# linuxcard.net
KiCad netlist of a schematic drawn in Altium Designer
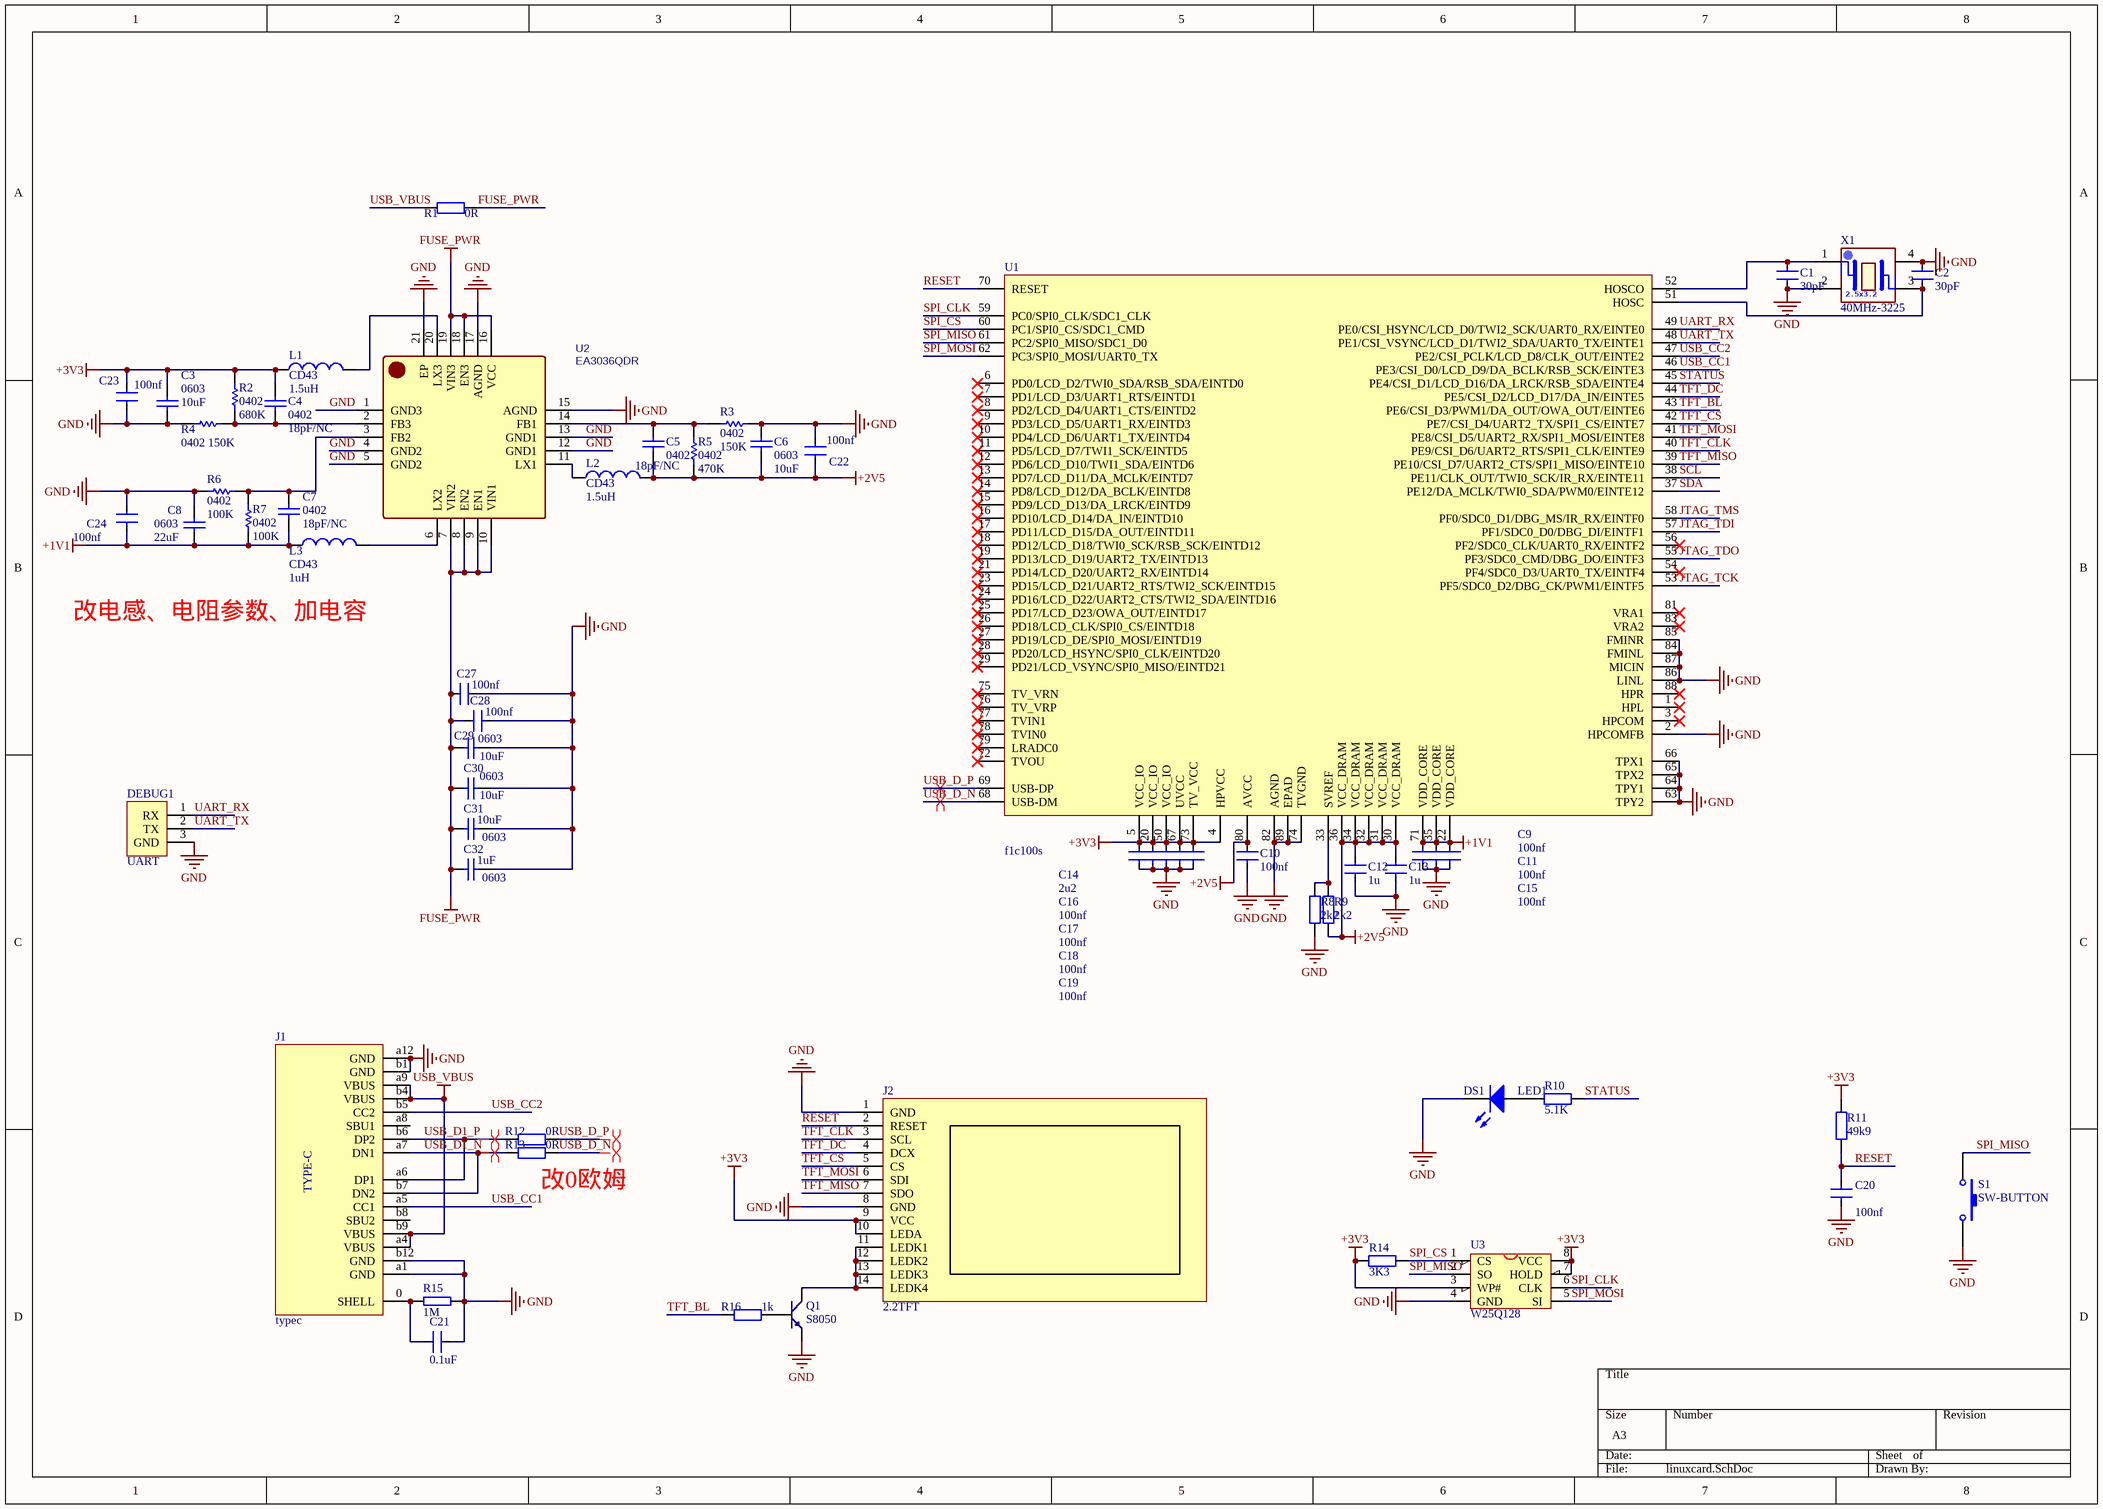
[diagram p0: linuxcard.SchDoc]

(export (version "E")
  (design (tool "Eeschema 10.0.6"))
  (components
    (comp (ref "C1")
      (value "30pF")
      (footprint "魔法王子:C0402")
      (description "普通小电容")
      (libsource (lib "LIB_MANGO") (part "CAP"))
    )
    (comp (ref "C2")
      (value "30pF")
      (footprint "魔法王子:C0402")
      (description "普通小电容")
      (libsource (lib "LIB_MANGO") (part "CAP"))
    )
    (comp (ref "C3")
      (value "0603")
      (footprint "pcb2D3D库1108:C0603")
      (description "Capacitor")
      (fields (field (name "ALTIUM_VALUE") "10uF") (field (name "PUBLISHER") "Altium Limited"))
      (libsource (lib "Miscellaneous Devices") (part "Cap"))
    )
    (comp (ref "C4")
      (value "0402")
      (footprint "pcb2D3D库1108:C0402")
      (description "Capacitor")
      (fields (field (name "ALTIUM_VALUE") "18pF/NC") (field (name "PUBLISHER") "Altium Limited"))
      (libsource (lib "Miscellaneous Devices") (part "Cap"))
    )
    (comp (ref "C5")
      (value "0402")
      (footprint "pcb2D3D库1108:C0402")
      (description "Capacitor")
      (fields (field (name "ALTIUM_VALUE") "18pF/NC") (field (name "PUBLISHER") "Altium Limited"))
      (libsource (lib "Miscellaneous Devices") (part "Cap"))
    )
    (comp (ref "C6")
      (value "0603")
      (footprint "pcb2D3D库1108:C0603")
      (description "Capacitor")
      (fields (field (name "ALTIUM_VALUE") "10uF") (field (name "PUBLISHER") "Altium Limited"))
      (libsource (lib "Miscellaneous Devices") (part "Cap"))
    )
    (comp (ref "C7")
      (value "0402")
      (footprint "pcb2D3D库1108:C0402")
      (description "Capacitor")
      (fields (field (name "ALTIUM_VALUE") "18pF/NC") (field (name "PUBLISHER") "Altium Limited"))
      (libsource (lib "Miscellaneous Devices") (part "Cap"))
    )
    (comp (ref "C8")
      (value "0603")
      (footprint "pcb2D3D库1108:C0603")
      (description "Capacitor")
      (fields (field (name "ALTIUM_VALUE") "22uF") (field (name "PUBLISHER") "Altium Limited"))
      (libsource (lib "Miscellaneous Devices") (part "Cap"))
    )
    (comp (ref "C9")
      (value "100nf")
      (footprint "魔法王子:C0402")
      (description "普通小电容")
      (libsource (lib "LIB_MANGO") (part "CAP"))
    )
    (comp (ref "C10")
      (value "100nf")
      (footprint "魔法王子:C0402")
      (description "普通小电容")
      (libsource (lib "LIB_MANGO") (part "CAP"))
    )
    (comp (ref "C11")
      (value "100nf")
      (footprint "魔法王子:C0402")
      (description "普通小电容")
      (libsource (lib "LIB_MANGO") (part "CAP"))
    )
    (comp (ref "C12")
      (value "1u")
      (footprint "魔法王子:C0402")
      (description "普通小电容")
      (libsource (lib "LIB_MANGO") (part "CAP"))
    )
    (comp (ref "C13")
      (value "1u")
      (footprint "魔法王子:C0402")
      (description "普通小电容")
      (libsource (lib "LIB_MANGO") (part "CAP"))
    )
    (comp (ref "C14")
      (value "2u2")
      (footprint "魔法王子:C0402")
      (description "普通小电容")
      (libsource (lib "LIB_MANGO") (part "CAP"))
    )
    (comp (ref "C15")
      (value "100nf")
      (footprint "魔法王子:C0402")
      (description "普通小电容")
      (libsource (lib "LIB_MANGO") (part "CAP"))
    )
    (comp (ref "C16")
      (value "100nf")
      (footprint "魔法王子:C0402")
      (description "普通小电容")
      (libsource (lib "LIB_MANGO") (part "CAP"))
    )
    (comp (ref "C17")
      (value "100nf")
      (footprint "魔法王子:C0402")
      (description "普通小电容")
      (libsource (lib "LIB_MANGO") (part "CAP"))
    )
    (comp (ref "C18")
      (value "100nf")
      (footprint "魔法王子:C0402")
      (description "普通小电容")
      (libsource (lib "LIB_MANGO") (part "CAP"))
    )
    (comp (ref "C19")
      (value "100nf")
      (footprint "魔法王子:C0402")
      (description "普通小电容")
      (libsource (lib "LIB_MANGO") (part "CAP"))
    )
    (comp (ref "C20")
      (value "100nf")
      (footprint "魔法王子:C0402")
      (description "普通小电容")
      (libsource (lib "LIB_MANGO") (part "CAP"))
    )
    (comp (ref "C21")
      (value "0.1uF")
      (footprint "魔法王子:C0402")
      (description "普通小电容")
      (libsource (lib "LIB_MANGO") (part "CAP"))
    )
    (comp (ref "C22")
      (value "100nf")
      (footprint "C0402")
      (description "普通小电容")
      (libsource (lib "LIB_MANGO") (part "CAP"))
    )
    (comp (ref "C23")
      (value "100nf")
      (footprint "C0402")
      (description "普通小电容")
      (libsource (lib "LIB_MANGO") (part "CAP"))
    )
    (comp (ref "C24")
      (value "100nf")
      (footprint "C0402")
      (description "普通小电容")
      (libsource (lib "LIB_MANGO") (part "CAP"))
    )
    (comp (ref "C27")
      (value "100nf")
      (footprint "C0402")
      (description "普通小电容")
      (libsource (lib "LIB_MANGO") (part "CAP"))
    )
    (comp (ref "C28")
      (value "100nf")
      (footprint "魔法王子:C0402")
      (description "普通小电容")
      (libsource (lib "LIB_MANGO") (part "CAP"))
    )
    (comp (ref "C29")
      (value "0603")
      (footprint "C0603")
      (description "Capacitor")
      (fields (field (name "ALTIUM_VALUE") "10uF") (field (name "PUBLISHER") "Altium Limited"))
      (libsource (lib "Miscellaneous Devices") (part "Cap"))
    )
    (comp (ref "C30")
      (value "0603")
      (footprint "C0603")
      (description "Capacitor")
      (fields (field (name "ALTIUM_VALUE") "10uF") (field (name "PUBLISHER") "Altium Limited"))
      (libsource (lib "Miscellaneous Devices") (part "Cap"))
    )
    (comp (ref "C31")
      (value "0603")
      (footprint "C0603")
      (description "Capacitor")
      (fields (field (name "ALTIUM_VALUE") "10uF") (field (name "PUBLISHER") "Altium Limited"))
      (libsource (lib "Miscellaneous Devices") (part "Cap"))
    )
    (comp (ref "C32")
      (value "0603")
      (footprint "C0603")
      (description "Capacitor")
      (fields (field (name "ALTIUM_VALUE") "1uF") (field (name "PUBLISHER") "Altium Limited"))
      (libsource (lib "Miscellaneous Devices") (part "Cap"))
    )
    (comp (ref "DEBUG1") (value "UART") (footprint "魔法王子:UART") (libsource (lib "魔法王子") (part "UART_OUT")))
    (comp (ref "DS1")
      (value "LED1")
      (footprint "pcb2D3D库1108:LED0805")
      (description "Typical RED, GREEN, YELLOW, AMBER GaAs LED")
      (fields (field (name "PUBLISHER") "Altium Limited"))
      (libsource (lib "Explorer STM32F407封装库") (part "LED2"))
    )
    (comp (ref "J1") (value "typec") (footprint "魔法王子:USBC") (libsource (lib "魔法王子") (part "USBC")))
    (comp (ref "J2") (value "2.2TFT") (footprint "魔法王子:2.2TFT") (libsource (lib "魔法王子") (part "TFT2.2")))
    (comp (ref "L1")
      (value "CD43")
      (footprint "pcb2D3D库1108:L1210")
      (fields (field (name "ALTIUM_VALUE") "1.5uH") (field (name "PUBLISHER") "Altium Limited"))
      (libsource (lib "Miscellaneous Devices") (part "Inductor"))
    )
    (comp (ref "L2")
      (value "CD43")
      (footprint "pcb2D3D库1108:L1210")
      (fields (field (name "ALTIUM_VALUE") "1.5uH") (field (name "PUBLISHER") "Altium Limited"))
      (libsource (lib "Miscellaneous Devices") (part "Inductor"))
    )
    (comp (ref "L3")
      (value "CD43")
      (footprint "pcb2D3D库1108:L1210")
      (fields (field (name "ALTIUM_VALUE") "1uH") (field (name "PUBLISHER") "Altium Limited"))
      (libsource (lib "Miscellaneous Devices") (part "Inductor"))
    )
    (comp (ref "Q1")
      (value "S8050")
      (footprint "魔法王子:sot-23")
      (description "8050/BCW846/BCW847")
      (libsource (lib "Explorer STM32F407封装库") (part "NPN"))
    )
    (comp (ref "R1")
      (value "0R")
      (footprint "pcb2D3D库1108:R0805")
      (description "普通电阻")
      (libsource (lib "") (part "RES_1"))
    )
    (comp (ref "R2")
      (value "0402")
      (footprint "pcb2D3D库1108:R0402")
      (fields (field (name "ALTIUM_VALUE") "680K") (field (name "PUBLISHER") "Altium Limited"))
      (libsource (lib "Miscellaneous Devices") (part "Res1"))
    )
    (comp (ref "R3")
      (value "0402")
      (footprint "pcb2D3D库1108:R0402")
      (description "Resistor")
      (fields (field (name "ALTIUM_VALUE") "150K") (field (name "PUBLISHER") "Altium Limited"))
      (libsource (lib "Miscellaneous Devices") (part "Res1"))
    )
    (comp (ref "R4")
      (value "0402")
      (footprint "pcb2D3D库1108:R0402")
      (description "Resistor")
      (fields (field (name "ALTIUM_VALUE") "150K") (field (name "PUBLISHER") "Altium Limited"))
      (libsource (lib "Miscellaneous Devices") (part "Res1"))
    )
    (comp (ref "R5")
      (value "0402")
      (footprint "pcb2D3D库1108:R0402")
      (fields (field (name "ALTIUM_VALUE") "470K") (field (name "PUBLISHER") "Altium Limited"))
      (libsource (lib "Miscellaneous Devices") (part "Res1"))
    )
    (comp (ref "R6")
      (value "0402")
      (footprint "pcb2D3D库1108:R0402")
      (fields (field (name "ALTIUM_VALUE") "100K") (field (name "PUBLISHER") "Altium Limited"))
      (libsource (lib "Miscellaneous Devices") (part "Res1"))
    )
    (comp (ref "R7")
      (value "0402")
      (footprint "pcb2D3D库1108:R0402")
      (fields (field (name "ALTIUM_VALUE") "100K") (field (name "PUBLISHER") "Altium Limited"))
      (libsource (lib "Miscellaneous Devices") (part "Res1"))
    )
    (comp (ref "R8")
      (value "2k2")
      (footprint "魔法王子:R0402")
      (description "普通电阻")
      (libsource (lib "LIB_MANGO") (part "RES"))
    )
    (comp (ref "R9")
      (value "2k2")
      (footprint "魔法王子:R0402")
      (description "普通电阻")
      (libsource (lib "LIB_MANGO") (part "RES"))
    )
    (comp (ref "R10")
      (value "5.1K")
      (footprint "魔法王子:R0402")
      (description "普通电阻")
      (libsource (lib "") (part "RES_1"))
    )
    (comp (ref "R11")
      (value "49k9")
      (footprint "魔法王子:R0402")
      (description "普通电阻")
      (libsource (lib "LIB_MANGO") (part "RES"))
    )
    (comp (ref "R12")
      (value "0R")
      (footprint "魔法王子:R0402")
      (description "普通电阻")
      (libsource (lib "") (part "RES_1"))
    )
    (comp (ref "R13")
      (value "0R")
      (footprint "魔法王子:R0402")
      (description "普通电阻")
      (libsource (lib "") (part "RES_1"))
    )
    (comp (ref "R14")
      (value "3K3")
      (footprint "魔法王子:R0402")
      (description "普通电阻")
      (libsource (lib "") (part "RES_2"))
    )
    (comp (ref "R15") (value "1M") (footprint "魔法王子:R0402") (libsource (lib "电阻") (part "0805正")))
    (comp (ref "R16")
      (value "1k")
      (footprint "魔法王子:R0402")
      (description "普通电阻")
      (libsource (lib "") (part "RES_1"))
    )
    (comp (ref "S1")
      (value "SW-BUTTON")
      (footprint "pcb2D3D库1108:KEY-SMD1")
      (libsource (lib "LIB_MANGO") (part "SW-BUTTON"))
    )
    (comp (ref "U1") (value "f1c100s") (footprint "魔法王子:F1C100S") (libsource (lib "魔法王子") (part "f1c100s")))
    (comp (ref "U2")
      (value "EA3036QDR")
      (footprint "魔法王子:ea3036")
      (fields (field (name "BOM_SUPPLIER PART") "C111587"))
      (libsource (lib "IC") (part "EA3036QDR"))
    )
    (comp (ref "U3")
      (value "W25Q128")
      (footprint "pcb2D3D库1108:SOIC8")
      (description "W25X16;SST25VF016;MX25L1605")
      (libsource (lib "Explorer STM32F407封装库") (part "W25X16"))
    )
    (comp (ref "X1")
      (value "40MHz-3225")
      (footprint "pcb2D3D库1108:XTAL-3225")
      (libsource (lib "LIB_MANGO") (part "XTAL3225"))
    )
  )
  (nets
    (net (code "1") (name "+1V1") (class "Default")
      (node (ref "C11") (pin "2") (pinfunction "2_2") (pintype "passive"))
      (node (ref "C15") (pin "2") (pinfunction "2_2") (pintype "passive"))
      (node (ref "C24") (pin "1") (pinfunction "1_1") (pintype "passive"))
      (node (ref "C7") (pin "1") (pinfunction "1_1") (pintype "passive"))
      (node (ref "C8") (pin "2") (pinfunction "2_2") (pintype "passive"))
      (node (ref "C9") (pin "2") (pinfunction "2_2") (pintype "passive"))
      (node (ref "L3") (pin "1") (pinfunction "1_1") (pintype "passive"))
      (node (ref "R7") (pin "1") (pinfunction "1_1") (pintype "passive"))
      (node (ref "U1") (pin "22") (pinfunction "VDD_CORE_22") (pintype "passive"))
      (node (ref "U1") (pin "35") (pinfunction "VDD_CORE_35") (pintype "passive"))
      (node (ref "U1") (pin "71") (pinfunction "VDD_CORE_71") (pintype "passive"))
    )
    (net (code "2") (name "+2V5") (class "Default")
      (node (ref "C10") (pin "2") (pinfunction "2_2") (pintype "passive"))
      (node (ref "C12") (pin "2") (pinfunction "2_2") (pintype "passive"))
      (node (ref "C13") (pin "2") (pinfunction "2_2") (pintype "passive"))
      (node (ref "C22") (pin "1") (pinfunction "1_1") (pintype "passive"))
      (node (ref "C5") (pin "1") (pinfunction "1_1") (pintype "passive"))
      (node (ref "C6") (pin "1") (pinfunction "1_1") (pintype "passive"))
      (node (ref "L2") (pin "2") (pinfunction "2_2") (pintype "passive"))
      (node (ref "R5") (pin "2") (pinfunction "2_2") (pintype "passive"))
      (node (ref "R9") (pin "2") (pinfunction "2_2") (pintype "passive"))
      (node (ref "U1") (pin "30") (pinfunction "VCC_DRAM_30") (pintype "passive"))
      (node (ref "U1") (pin "31") (pinfunction "VCC_DRAM_31") (pintype "passive"))
      (node (ref "U1") (pin "32") (pinfunction "VCC_DRAM_32") (pintype "passive"))
      (node (ref "U1") (pin "34") (pinfunction "VCC_DRAM_34") (pintype "passive"))
      (node (ref "U1") (pin "36") (pinfunction "VCC_DRAM_36") (pintype "passive"))
      (node (ref "U1") (pin "80") (pinfunction "AVCC_80") (pintype "passive"))
    )
    (net (code "3") (name "+3V3") (class "Default")
      (node (ref "C14") (pin "2") (pinfunction "2_2") (pintype "passive"))
      (node (ref "C16") (pin "2") (pinfunction "2_2") (pintype "passive"))
      (node (ref "C17") (pin "2") (pinfunction "2_2") (pintype "passive"))
      (node (ref "C18") (pin "2") (pinfunction "2_2") (pintype "passive"))
      (node (ref "C19") (pin "2") (pinfunction "2_2") (pintype "passive"))
      (node (ref "C23") (pin "2") (pinfunction "2_2") (pintype "passive"))
      (node (ref "C3") (pin "1") (pinfunction "1_1") (pintype "passive"))
      (node (ref "C4") (pin "1") (pinfunction "1_1") (pintype "passive"))
      (node (ref "J2") (pin "10") (pinfunction "LEDA_10") (pintype "passive"))
      (node (ref "J2") (pin "9") (pinfunction "VCC_9") (pintype "passive"))
      (node (ref "L1") (pin "1") (pinfunction "1_1") (pintype "passive"))
      (node (ref "R11") (pin "1") (pinfunction "1_1") (pintype "passive"))
      (node (ref "R14") (pin "2") (pinfunction "2_2") (pintype "passive"))
      (node (ref "R2") (pin "2") (pinfunction "2_2") (pintype "passive"))
      (node (ref "U1") (pin "20") (pinfunction "VCC_IO_20") (pintype "passive"))
      (node (ref "U1") (pin "4") (pinfunction "HPVCC_4") (pintype "passive"))
      (node (ref "U1") (pin "5") (pinfunction "VCC_IO_5") (pintype "passive"))
      (node (ref "U1") (pin "50") (pinfunction "VCC_IO_50") (pintype "passive"))
      (node (ref "U1") (pin "67") (pinfunction "UVCC_67") (pintype "passive"))
      (node (ref "U1") (pin "73") (pinfunction "TV_VCC_73") (pintype "passive"))
      (node (ref "U3") (pin "3") (pinfunction "WP#_3") (pintype "passive"))
      (node (ref "U3") (pin "7") (pinfunction "HOLD_7") (pintype "passive"))
      (node (ref "U3") (pin "8") (pinfunction "VCC_8") (pintype "passive"))
    )
    (net (code "4") (name "/JTAG_TCK") (class "Default")
      (node (ref "U1") (pin "53") (pinfunction "PF5/SDC0_D2/DBG_CK/PWM1/EINTF5_53") (pintype "passive"))
    )
    (net (code "5") (name "/JTAG_TDI") (class "Default")
      (node (ref "U1") (pin "57") (pinfunction "PF1/SDC0_D0/DBG_DI/EINTF1_57") (pintype "passive"))
    )
    (net (code "6") (name "/JTAG_TDO") (class "Default")
      (node (ref "U1") (pin "55") (pinfunction "PF3/SDC0_CMD/DBG_DO/EINTF3_55") (pintype "passive"))
    )
    (net (code "7") (name "/JTAG_TMS") (class "Default")
      (node (ref "U1") (pin "58") (pinfunction "PF0/SDC0_D1/DBG_MS/IR_RX/EINTF0_58") (pintype "passive"))
    )
    (net (code "8") (name "/RESET") (class "Default")
      (node (ref "C20") (pin "2") (pinfunction "2_2") (pintype "passive"))
      (node (ref "J2") (pin "2") (pinfunction "RESET_2") (pintype "passive"))
      (node (ref "R11") (pin "2") (pinfunction "2_2") (pintype "passive"))
      (node (ref "U1") (pin "70") (pinfunction "RESET_70") (pintype "passive"))
    )
    (net (code "9") (name "/SCL") (class "Default")
      (node (ref "U1") (pin "38") (pinfunction "PE11/CLK_OUT/TWI0_SCK/IR_RX/EINTE11_38") (pintype "passive"))
    )
    (net (code "10") (name "/SDA") (class "Default")
      (node (ref "U1") (pin "37") (pinfunction "PE12/DA_MCLK/TWI0_SDA/PWM0/EINTE12_37") (pintype "passive"))
    )
    (net (code "11") (name "/SPI_CLK") (class "Default")
      (node (ref "U1") (pin "59") (pinfunction "PC0/SPI0_CLK/SDC1_CLK_59") (pintype "passive"))
      (node (ref "U3") (pin "6") (pinfunction "CLK_6") (pintype "passive"))
    )
    (net (code "12") (name "/SPI_CS") (class "Default")
      (node (ref "R14") (pin "1") (pinfunction "1_1") (pintype "passive"))
      (node (ref "U1") (pin "60") (pinfunction "PC1/SPI0_CS/SDC1_CMD_60") (pintype "passive"))
      (node (ref "U3") (pin "1") (pinfunction "CS_1") (pintype "passive"))
    )
    (net (code "13") (name "/SPI_MISO") (class "Default")
      (node (ref "S1") (pin "1") (pinfunction "1_1") (pintype "passive"))
      (node (ref "U1") (pin "61") (pinfunction "PC2/SPI0_MISO/SDC1_D0_61") (pintype "passive"))
      (node (ref "U3") (pin "2") (pinfunction "SO_2") (pintype "passive"))
    )
    (net (code "14") (name "/SPI_MOSI") (class "Default")
      (node (ref "U1") (pin "62") (pinfunction "PC3/SPI0_MOSI/UART0_TX_62") (pintype "passive"))
      (node (ref "U3") (pin "5") (pinfunction "SI_5") (pintype "passive"))
    )
    (net (code "15") (name "/STATUS") (class "Default")
      (node (ref "R10") (pin "2") (pinfunction "2_2") (pintype "passive"))
      (node (ref "U1") (pin "45") (pinfunction "PE4/CSI_D1/LCD_D16/DA_LRCK/RSB_SDA/EINTE4_45") (pintype "passive"))
    )
    (net (code "16") (name "/TFT_BL") (class "Default")
      (node (ref "R16") (pin "1") (pinfunction "1_1") (pintype "passive"))
      (node (ref "U1") (pin "43") (pinfunction "PE6/CSI_D3/PWM1/DA_OUT/OWA_OUT/EINTE6_43") (pintype "passive"))
    )
    (net (code "17") (name "/TFT_CLK") (class "Default")
      (node (ref "J2") (pin "3") (pinfunction "SCL_3") (pintype "passive"))
      (node (ref "U1") (pin "40") (pinfunction "PE9/CSI_D6/UART2_RTS/SPI1_CLK/EINTE9_40") (pintype "passive"))
    )
    (net (code "18") (name "/TFT_CS") (class "Default")
      (node (ref "J2") (pin "5") (pinfunction "CS_5") (pintype "passive"))
      (node (ref "U1") (pin "42") (pinfunction "PE7/CSI_D4/UART2_TX/SPI1_CS/EINTE7_42") (pintype "passive"))
    )
    (net (code "19") (name "/TFT_DC") (class "Default")
      (node (ref "J2") (pin "4") (pinfunction "DCX_4") (pintype "passive"))
      (node (ref "U1") (pin "44") (pinfunction "PE5/CSI_D2/LCD_D17/DA_IN/EINTE5_44") (pintype "passive"))
    )
    (net (code "20") (name "/TFT_MISO") (class "Default")
      (node (ref "J2") (pin "7") (pinfunction "SDO_7") (pintype "passive"))
      (node (ref "U1") (pin "39") (pinfunction "PE10/CSI_D7/UART2_CTS/SPI1_MISO/EINTE10_39") (pintype "passive"))
    )
    (net (code "21") (name "/TFT_MOSI") (class "Default")
      (node (ref "J2") (pin "6") (pinfunction "SDI_6") (pintype "passive"))
      (node (ref "U1") (pin "41") (pinfunction "PE8/CSI_D5/UART2_RX/SPI1_MOSI/EINTE8_41") (pintype "passive"))
    )
    (net (code "22") (name "/UART_RX") (class "Default")
      (node (ref "DEBUG1") (pin "1") (pinfunction "RX_1") (pintype "passive"))
      (node (ref "U1") (pin "49") (pinfunction "PE0/CSI_HSYNC/LCD_D0/TWI2_SCK/UART0_RX/EINTE0_49") (pintype "passive"))
    )
    (net (code "23") (name "/UART_TX") (class "Default")
      (node (ref "DEBUG1") (pin "2") (pinfunction "TX_2") (pintype "passive"))
      (node (ref "U1") (pin "48") (pinfunction "PE1/CSI_VSYNC/LCD_D1/TWI2_SDA/UART0_TX/EINTE1_48") (pintype "passive"))
    )
    (net (code "24") (name "/USB_CC1") (class "Default")
      (node (ref "J1") (pin "a5") (pinfunction "CC1_a5") (pintype "passive"))
      (node (ref "U1") (pin "46") (pinfunction "PE3/CSI_D0/LCD_D9/DA_BCLK/RSB_SCK/EINTE3_46") (pintype "passive"))
    )
    (net (code "25") (name "/USB_CC2") (class "Default")
      (node (ref "J1") (pin "b5") (pinfunction "CC2_b5") (pintype "passive"))
      (node (ref "U1") (pin "47") (pinfunction "PE2/CSI_PCLK/LCD_D8/CLK_OUT/EINTE2_47") (pintype "passive"))
    )
    (net (code "26") (name "/USB_D1_N") (class "Default")
      (node (ref "J1") (pin "a7") (pinfunction "DN1_a7") (pintype "passive"))
      (node (ref "J1") (pin "b7") (pinfunction "DN2_b7") (pintype "passive"))
      (node (ref "R13") (pin "1") (pinfunction "1_1") (pintype "passive"))
    )
    (net (code "27") (name "/USB_D1_P") (class "Default")
      (node (ref "J1") (pin "a6") (pinfunction "DP1_a6") (pintype "passive"))
      (node (ref "J1") (pin "b6") (pinfunction "DP2_b6") (pintype "passive"))
      (node (ref "R12") (pin "1") (pinfunction "1_1") (pintype "passive"))
    )
    (net (code "28") (name "/USB_D_N") (class "Default")
      (node (ref "R13") (pin "2") (pinfunction "2_2") (pintype "passive"))
      (node (ref "U1") (pin "68") (pinfunction "USB-DM_68") (pintype "passive"))
    )
    (net (code "29") (name "/USB_D_P") (class "Default")
      (node (ref "R12") (pin "2") (pinfunction "2_2") (pintype "passive"))
      (node (ref "U1") (pin "69") (pinfunction "USB-DP_69") (pintype "passive"))
    )
    (net (code "30") (name "FUSE_PWR") (class "Default")
      (node (ref "C27") (pin "2") (pinfunction "2_2") (pintype "passive"))
      (node (ref "C28") (pin "2") (pinfunction "2_2") (pintype "passive"))
      (node (ref "C29") (pin "1") (pinfunction "1_1") (pintype "passive"))
      (node (ref "C30") (pin "1") (pinfunction "1_1") (pintype "passive"))
      (node (ref "C31") (pin "1") (pinfunction "1_1") (pintype "passive"))
      (node (ref "C32") (pin "1") (pinfunction "1_1") (pintype "passive"))
      (node (ref "R1") (pin "2") (pinfunction "2_2") (pintype "passive"))
      (node (ref "U2") (pin "10") (pinfunction "VIN1_10") (pintype "passive"))
      (node (ref "U2") (pin "16") (pinfunction "VCC_16") (pintype "passive"))
      (node (ref "U2") (pin "18") (pinfunction "EN3_18") (pintype "passive"))
      (node (ref "U2") (pin "19") (pinfunction "VIN3_19") (pintype "passive"))
      (node (ref "U2") (pin "7") (pinfunction "VIN2_7") (pintype "passive"))
      (node (ref "U2") (pin "8") (pinfunction "EN2_8") (pintype "passive"))
      (node (ref "U2") (pin "9") (pinfunction "EN1_9") (pintype "passive"))
    )
    (net (code "31") (name "GND") (class "Default")
      (node (ref "C1") (pin "1") (pinfunction "1_1") (pintype "passive"))
      (node (ref "C10") (pin "1") (pinfunction "1_1") (pintype "passive"))
      (node (ref "C11") (pin "1") (pinfunction "1_1") (pintype "passive"))
      (node (ref "C12") (pin "1") (pinfunction "1_1") (pintype "passive"))
      (node (ref "C13") (pin "1") (pinfunction "1_1") (pintype "passive"))
      (node (ref "C14") (pin "1") (pinfunction "1_1") (pintype "passive"))
      (node (ref "C15") (pin "1") (pinfunction "1_1") (pintype "passive"))
      (node (ref "C16") (pin "1") (pinfunction "1_1") (pintype "passive"))
      (node (ref "C17") (pin "1") (pinfunction "1_1") (pintype "passive"))
      (node (ref "C18") (pin "1") (pinfunction "1_1") (pintype "passive"))
      (node (ref "C19") (pin "1") (pinfunction "1_1") (pintype "passive"))
      (node (ref "C2") (pin "2") (pinfunction "2_2") (pintype "passive"))
      (node (ref "C20") (pin "1") (pinfunction "1_1") (pintype "passive"))
      (node (ref "C21") (pin "1") (pinfunction "1_1") (pintype "passive"))
      (node (ref "C22") (pin "2") (pinfunction "2_2") (pintype "passive"))
      (node (ref "C23") (pin "1") (pinfunction "1_1") (pintype "passive"))
      (node (ref "C24") (pin "2") (pinfunction "2_2") (pintype "passive"))
      (node (ref "C27") (pin "1") (pinfunction "1_1") (pintype "passive"))
      (node (ref "C28") (pin "1") (pinfunction "1_1") (pintype "passive"))
      (node (ref "C29") (pin "2") (pinfunction "2_2") (pintype "passive"))
      (node (ref "C3") (pin "2") (pinfunction "2_2") (pintype "passive"))
      (node (ref "C30") (pin "2") (pinfunction "2_2") (pintype "passive"))
      (node (ref "C31") (pin "2") (pinfunction "2_2") (pintype "passive"))
      (node (ref "C32") (pin "2") (pinfunction "2_2") (pintype "passive"))
      (node (ref "C6") (pin "2") (pinfunction "2_2") (pintype "passive"))
      (node (ref "C8") (pin "1") (pinfunction "1_1") (pintype "passive"))
      (node (ref "C9") (pin "1") (pinfunction "1_1") (pintype "passive"))
      (node (ref "DEBUG1") (pin "3") (pinfunction "GND_3") (pintype "passive"))
      (node (ref "DS1") (pin "2") (pinfunction "K_2") (pintype "passive"))
      (node (ref "J1") (pin "a1") (pinfunction "GND_a1") (pintype "passive"))
      (node (ref "J1") (pin "a12") (pinfunction "GND_a12") (pintype "passive"))
      (node (ref "J1") (pin "b1") (pinfunction "GND_b1") (pintype "passive"))
      (node (ref "J1") (pin "b12") (pinfunction "GND_b12") (pintype "passive"))
      (node (ref "J2") (pin "1") (pinfunction "GND_1") (pintype "passive"))
      (node (ref "J2") (pin "8") (pinfunction "GND_8") (pintype "passive"))
      (node (ref "Q1") (pin "1") (pinfunction "E_1") (pintype "passive"))
      (node (ref "R15") (pin "1") (pinfunction "1_1") (pintype "passive"))
      (node (ref "R3") (pin "2") (pinfunction "2_2") (pintype "passive"))
      (node (ref "R4") (pin "2") (pinfunction "2_2") (pintype "passive"))
      (node (ref "R6") (pin "2") (pinfunction "2_2") (pintype "passive"))
      (node (ref "R8") (pin "2") (pinfunction "2_2") (pintype "passive"))
      (node (ref "S1") (pin "2") (pinfunction "2_2") (pintype "passive"))
      (node (ref "U1") (pin "2") (pinfunction "HPCOMFB_2") (pintype "passive"))
      (node (ref "U1") (pin "63") (pinfunction "TPY2_63") (pintype "passive"))
      (node (ref "U1") (pin "64") (pinfunction "TPY1_64") (pintype "passive"))
      (node (ref "U1") (pin "65") (pinfunction "TPX2_65") (pintype "passive"))
      (node (ref "U1") (pin "66") (pinfunction "TPX1_66") (pintype "passive"))
      (node (ref "U1") (pin "74") (pinfunction "TVGND_74") (pintype "passive"))
      (node (ref "U1") (pin "82") (pinfunction "AGND_82") (pintype "passive"))
      (node (ref "U1") (pin "84") (pinfunction "FMINL_84") (pintype "passive"))
      (node (ref "U1") (pin "85") (pinfunction "FMINR_85") (pintype "passive"))
      (node (ref "U1") (pin "86") (pinfunction "LINL_86") (pintype "passive"))
      (node (ref "U1") (pin "87") (pinfunction "MICIN_87") (pintype "passive"))
      (node (ref "U1") (pin "89") (pinfunction "EPAD_89") (pintype "passive"))
      (node (ref "U2") (pin "1") (pinfunction "GND3_1") (pintype "passive"))
      (node (ref "U2") (pin "12") (pinfunction "GND1_12") (pintype "passive"))
      (node (ref "U2") (pin "13") (pinfunction "GND1_13") (pintype "passive"))
      (node (ref "U2") (pin "15") (pinfunction "AGND_15") (pintype "passive"))
      (node (ref "U2") (pin "17") (pinfunction "AGND_17") (pintype "passive"))
      (node (ref "U2") (pin "21") (pinfunction "EP_21") (pintype "passive"))
      (node (ref "U2") (pin "4") (pinfunction "GND2_4") (pintype "passive"))
      (node (ref "U2") (pin "5") (pinfunction "GND2_5") (pintype "passive"))
      (node (ref "U3") (pin "4") (pinfunction "GND_4") (pintype "passive"))
      (node (ref "X1") (pin "2") (pinfunction "NC1_2") (pintype "passive"))
      (node (ref "X1") (pin "4") (pinfunction "NC2_4") (pintype "passive"))
    )
    (net (code "32") (name "Net-(DS1-A)") (class "Default")
      (node (ref "DS1") (pin "1") (pinfunction "A_1") (pintype "passive"))
      (node (ref "R10") (pin "1") (pinfunction "1_1") (pintype "passive"))
    )
    (net (code "33") (name "Net-(J1-SHELL)") (class "Default")
      (node (ref "C21") (pin "2") (pinfunction "2_2") (pintype "passive"))
      (node (ref "J1") (pin "0") (pinfunction "SHELL_0") (pintype "passive"))
      (node (ref "R15") (pin "2") (pinfunction "2_2") (pintype "passive"))
    )
    (net (code "34") (name "Net-(J2-LEDK1)") (class "Default")
      (node (ref "J2") (pin "11") (pinfunction "LEDK1_11") (pintype "passive"))
      (node (ref "J2") (pin "12") (pinfunction "LEDK2_12") (pintype "passive"))
      (node (ref "J2") (pin "13") (pinfunction "LEDK3_13") (pintype "passive"))
      (node (ref "J2") (pin "14") (pinfunction "LEDK4_14") (pintype "passive"))
      (node (ref "Q1") (pin "3") (pinfunction "C_3") (pintype "passive"))
    )
    (net (code "35") (name "Net-(Q1-B)") (class "Default")
      (node (ref "Q1") (pin "2") (pinfunction "B_2") (pintype "passive"))
      (node (ref "R16") (pin "2") (pinfunction "2_2") (pintype "passive"))
    )
    (net (code "36") (name "Net-(U1-HOSC)") (class "Default")
      (node (ref "C2") (pin "1") (pinfunction "1_1") (pintype "passive"))
      (node (ref "U1") (pin "51") (pinfunction "HOSC_51") (pintype "passive"))
      (node (ref "X1") (pin "3") (pinfunction "X2_3") (pintype "passive"))
    )
    (net (code "37") (name "Net-(U1-HOSCO)") (class "Default")
      (node (ref "C1") (pin "2") (pinfunction "2_2") (pintype "passive"))
      (node (ref "U1") (pin "52") (pinfunction "HOSCO_52") (pintype "passive"))
      (node (ref "X1") (pin "1") (pinfunction "X1_1") (pintype "passive"))
    )
    (net (code "38") (name "Net-(U1-SVREF)") (class "Default")
      (node (ref "R8") (pin "1") (pinfunction "1_1") (pintype "passive"))
      (node (ref "R9") (pin "1") (pinfunction "1_1") (pintype "passive"))
      (node (ref "U1") (pin "33") (pinfunction "SVREF_33") (pintype "passive"))
    )
    (net (code "39") (name "Net-(U2-FB1)") (class "Default")
      (node (ref "C5") (pin "2") (pinfunction "2_2") (pintype "passive"))
      (node (ref "R3") (pin "1") (pinfunction "1_1") (pintype "passive"))
      (node (ref "R5") (pin "1") (pinfunction "1_1") (pintype "passive"))
      (node (ref "U2") (pin "14") (pinfunction "FB1_14") (pintype "passive"))
    )
    (net (code "40") (name "Net-(U2-FB2)") (class "Default")
      (node (ref "C7") (pin "2") (pinfunction "2_2") (pintype "passive"))
      (node (ref "R6") (pin "1") (pinfunction "1_1") (pintype "passive"))
      (node (ref "R7") (pin "2") (pinfunction "2_2") (pintype "passive"))
      (node (ref "U2") (pin "3") (pinfunction "FB2_3") (pintype "passive"))
    )
    (net (code "41") (name "Net-(U2-FB3)") (class "Default")
      (node (ref "C4") (pin "2") (pinfunction "2_2") (pintype "passive"))
      (node (ref "R2") (pin "1") (pinfunction "1_1") (pintype "passive"))
      (node (ref "R4") (pin "1") (pinfunction "1_1") (pintype "passive"))
      (node (ref "U2") (pin "2") (pinfunction "FB3_2") (pintype "passive"))
    )
    (net (code "42") (name "Net-(U2-LX1)") (class "Default")
      (node (ref "L2") (pin "1") (pinfunction "1_1") (pintype "passive"))
      (node (ref "U2") (pin "11") (pinfunction "LX1_11") (pintype "passive"))
    )
    (net (code "43") (name "Net-(U2-LX2)") (class "Default")
      (node (ref "L3") (pin "2") (pinfunction "2_2") (pintype "passive"))
      (node (ref "U2") (pin "6") (pinfunction "LX2_6") (pintype "passive"))
    )
    (net (code "44") (name "Net-(U2-LX3)") (class "Default")
      (node (ref "L1") (pin "2") (pinfunction "2_2") (pintype "passive"))
      (node (ref "U2") (pin "20") (pinfunction "LX3_20") (pintype "passive"))
    )
    (net (code "45") (name "USB_VBUS") (class "Default")
      (node (ref "J1") (pin "a4") (pinfunction "VBUS_a4") (pintype "passive"))
      (node (ref "J1") (pin "a9") (pinfunction "VBUS_a9") (pintype "passive"))
      (node (ref "J1") (pin "b4") (pinfunction "VBUS_b4") (pintype "passive"))
      (node (ref "J1") (pin "b9") (pinfunction "VBUS_b9") (pintype "passive"))
      (node (ref "R1") (pin "1") (pinfunction "1_1") (pintype "passive"))
    )
    (net (code "46") (name "unconnected-(J1-SBU1-Pada8)") (class "Default")
      (node (ref "J1") (pin "a8") (pinfunction "SBU1_a8") (pintype "passive"))
    )
    (net (code "47") (name "unconnected-(J1-SBU2-Padb8)") (class "Default")
      (node (ref "J1") (pin "b8") (pinfunction "SBU2_b8") (pintype "passive"))
    )
    (net (code "48") (name "unconnected-(U1-HPCOM-Pad3)") (class "Default")
      (node (ref "U1") (pin "3") (pinfunction "HPCOM_3") (pintype "passive+no_connect"))
    )
    (net (code "49") (name "unconnected-(U1-HPL-Pad1)") (class "Default")
      (node (ref "U1") (pin "1") (pinfunction "HPL_1") (pintype "passive+no_connect"))
    )
    (net (code "50") (name "unconnected-(U1-HPR-Pad88)") (class "Default")
      (node (ref "U1") (pin "88") (pinfunction "HPR_88") (pintype "passive+no_connect"))
    )
    (net (code "51") (name "unconnected-(U1-LRADC0-Pad79)") (class "Default")
      (node (ref "U1") (pin "79") (pinfunction "LRADC0_79") (pintype "passive+no_connect"))
    )
    (net (code "52") (name "unconnected-(U1-PD0{slash}LCD_D2{slash}TWI0_SDA{slash}RSB_SDA{slash}EINTD0-Pad6)") (class "Default")
      (node (ref "U1") (pin "6") (pinfunction "PD0/LCD_D2/TWI0_SDA/RSB_SDA/EINTD0_6") (pintype "passive+no_connect"))
    )
    (net (code "53") (name "unconnected-(U1-PD1{slash}LCD_D3{slash}UART1_RTS{slash}EINTD1-Pad7)") (class "Default")
      (node (ref "U1") (pin "7") (pinfunction "PD1/LCD_D3/UART1_RTS/EINTD1_7") (pintype "passive+no_connect"))
    )
    (net (code "54") (name "unconnected-(U1-PD2{slash}LCD_D4{slash}UART1_CTS{slash}EINTD2-Pad8)") (class "Default")
      (node (ref "U1") (pin "8") (pinfunction "PD2/LCD_D4/UART1_CTS/EINTD2_8") (pintype "passive+no_connect"))
    )
    (net (code "55") (name "unconnected-(U1-PD3{slash}LCD_D5{slash}UART1_RX{slash}EINTD3-Pad9)") (class "Default")
      (node (ref "U1") (pin "9") (pinfunction "PD3/LCD_D5/UART1_RX/EINTD3_9") (pintype "passive+no_connect"))
    )
    (net (code "56") (name "unconnected-(U1-PD4{slash}LCD_D6{slash}UART1_TX{slash}EINTD4-Pad10)") (class "Default")
      (node (ref "U1") (pin "10") (pinfunction "PD4/LCD_D6/UART1_TX/EINTD4_10") (pintype "passive+no_connect"))
    )
    (net (code "57") (name "unconnected-(U1-PD5{slash}LCD_D7{slash}TWI1_SCK{slash}EINTD5-Pad11)") (class "Default")
      (node (ref "U1") (pin "11") (pinfunction "PD5/LCD_D7/TWI1_SCK/EINTD5_11") (pintype "passive+no_connect"))
    )
    (net (code "58") (name "unconnected-(U1-PD6{slash}LCD_D10{slash}TWI1_SDA{slash}EINTD6-Pad12)") (class "Default")
      (node (ref "U1") (pin "12") (pinfunction "PD6/LCD_D10/TWI1_SDA/EINTD6_12") (pintype "passive+no_connect"))
    )
    (net (code "59") (name "unconnected-(U1-PD7{slash}LCD_D11{slash}DA_MCLK{slash}EINTD7-Pad13)") (class "Default")
      (node (ref "U1") (pin "13") (pinfunction "PD7/LCD_D11/DA_MCLK/EINTD7_13") (pintype "passive+no_connect"))
    )
    (net (code "60") (name "unconnected-(U1-PD8{slash}LCD_D12{slash}DA_BCLK{slash}EINTD8-Pad14)") (class "Default")
      (node (ref "U1") (pin "14") (pinfunction "PD8/LCD_D12/DA_BCLK/EINTD8_14") (pintype "passive+no_connect"))
    )
    (net (code "61") (name "unconnected-(U1-PD9{slash}LCD_D13{slash}DA_LRCK{slash}EINTD9-Pad15)") (class "Default")
      (node (ref "U1") (pin "15") (pinfunction "PD9/LCD_D13/DA_LRCK/EINTD9_15") (pintype "passive+no_connect"))
    )
    (net (code "62") (name "unconnected-(U1-PD10{slash}LCD_D14{slash}DA_IN{slash}EINTD10-Pad16)") (class "Default")
      (node (ref "U1") (pin "16") (pinfunction "PD10/LCD_D14/DA_IN/EINTD10_16") (pintype "passive+no_connect"))
    )
    (net (code "63") (name "unconnected-(U1-PD11{slash}LCD_D15{slash}DA_OUT{slash}EINTD11-Pad17)") (class "Default")
      (node (ref "U1") (pin "17") (pinfunction "PD11/LCD_D15/DA_OUT/EINTD11_17") (pintype "passive+no_connect"))
    )
    (net (code "64") (name "unconnected-(U1-PD12{slash}LCD_D18{slash}TWI0_SCK{slash}RSB_SCK{slash}EINTD12-Pad18)") (class "Default")
      (node (ref "U1") (pin "18") (pinfunction "PD12/LCD_D18/TWI0_SCK/RSB_SCK/EINTD12_18") (pintype "passive+no_connect"))
    )
    (net (code "65") (name "unconnected-(U1-PD13{slash}LCD_D19{slash}UART2_TX{slash}EINTD13-Pad19)") (class "Default")
      (node (ref "U1") (pin "19") (pinfunction "PD13/LCD_D19/UART2_TX/EINTD13_19") (pintype "passive+no_connect"))
    )
    (net (code "66") (name "unconnected-(U1-PD14{slash}LCD_D20{slash}UART2_RX{slash}EINTD14-Pad21)") (class "Default")
      (node (ref "U1") (pin "21") (pinfunction "PD14/LCD_D20/UART2_RX/EINTD14_21") (pintype "passive+no_connect"))
    )
    (net (code "67") (name "unconnected-(U1-PD15{slash}LCD_D21{slash}UART2_RTS{slash}TWI2_SCK{slash}EINTD15-Pad23)") (class "Default")
      (node (ref "U1") (pin "23") (pinfunction "PD15/LCD_D21/UART2_RTS/TWI2_SCK/EINTD15_23") (pintype "passive+no_connect"))
    )
    (net (code "68") (name "unconnected-(U1-PD16{slash}LCD_D22{slash}UART2_CTS{slash}TWI2_SDA{slash}EINTD16-Pad24)") (class "Default")
      (node (ref "U1") (pin "24") (pinfunction "PD16/LCD_D22/UART2_CTS/TWI2_SDA/EINTD16_24") (pintype "passive+no_connect"))
    )
    (net (code "69") (name "unconnected-(U1-PD17{slash}LCD_D23{slash}OWA_OUT{slash}EINTD17-Pad25)") (class "Default")
      (node (ref "U1") (pin "25") (pinfunction "PD17/LCD_D23/OWA_OUT/EINTD17_25") (pintype "passive+no_connect"))
    )
    (net (code "70") (name "unconnected-(U1-PD18{slash}LCD_CLK{slash}SPI0_CS{slash}EINTD18-Pad26)") (class "Default")
      (node (ref "U1") (pin "26") (pinfunction "PD18/LCD_CLK/SPI0_CS/EINTD18_26") (pintype "passive+no_connect"))
    )
    (net (code "71") (name "unconnected-(U1-PD19{slash}LCD_DE{slash}SPI0_MOSI{slash}EINTD19-Pad27)") (class "Default")
      (node (ref "U1") (pin "27") (pinfunction "PD19/LCD_DE/SPI0_MOSI/EINTD19_27") (pintype "passive+no_connect"))
    )
    (net (code "72") (name "unconnected-(U1-PD20{slash}LCD_HSYNC{slash}SPI0_CLK{slash}EINTD20-Pad28)") (class "Default")
      (node (ref "U1") (pin "28") (pinfunction "PD20/LCD_HSYNC/SPI0_CLK/EINTD20_28") (pintype "passive+no_connect"))
    )
    (net (code "73") (name "unconnected-(U1-PD21{slash}LCD_VSYNC{slash}SPI0_MISO{slash}EINTD21-Pad29)") (class "Default")
      (node (ref "U1") (pin "29") (pinfunction "PD21/LCD_VSYNC/SPI0_MISO/EINTD21_29") (pintype "passive+no_connect"))
    )
    (net (code "74") (name "unconnected-(U1-PF2{slash}SDC0_CLK{slash}UART0_RX{slash}EINTF2-Pad56)") (class "Default")
      (node (ref "U1") (pin "56") (pinfunction "PF2/SDC0_CLK/UART0_RX/EINTF2_56") (pintype "passive+no_connect"))
    )
    (net (code "75") (name "unconnected-(U1-PF4{slash}SDC0_D3{slash}UART0_TX{slash}EINTF4-Pad54)") (class "Default")
      (node (ref "U1") (pin "54") (pinfunction "PF4/SDC0_D3/UART0_TX/EINTF4_54") (pintype "passive+no_connect"))
    )
    (net (code "76") (name "unconnected-(U1-TVIN0-Pad78)") (class "Default")
      (node (ref "U1") (pin "78") (pinfunction "TVIN0_78") (pintype "passive+no_connect"))
    )
    (net (code "77") (name "unconnected-(U1-TVIN1-Pad77)") (class "Default")
      (node (ref "U1") (pin "77") (pinfunction "TVIN1_77") (pintype "passive+no_connect"))
    )
    (net (code "78") (name "unconnected-(U1-TVOU-Pad72)") (class "Default")
      (node (ref "U1") (pin "72") (pinfunction "TVOU_72") (pintype "passive+no_connect"))
    )
    (net (code "79") (name "unconnected-(U1-TV_VRN-Pad75)") (class "Default")
      (node (ref "U1") (pin "75") (pinfunction "TV_VRN_75") (pintype "passive+no_connect"))
    )
    (net (code "80") (name "unconnected-(U1-TV_VRP-Pad76)") (class "Default")
      (node (ref "U1") (pin "76") (pinfunction "TV_VRP_76") (pintype "passive+no_connect"))
    )
    (net (code "81") (name "unconnected-(U1-VRA1-Pad81)") (class "Default")
      (node (ref "U1") (pin "81") (pinfunction "VRA1_81") (pintype "passive+no_connect"))
    )
    (net (code "82") (name "unconnected-(U1-VRA2-Pad83)") (class "Default")
      (node (ref "U1") (pin "83") (pinfunction "VRA2_83") (pintype "passive+no_connect"))
    )
  )
)
